# ML8511_Breakout.net
KiCad netlist of a schematic drawn in EAGLE
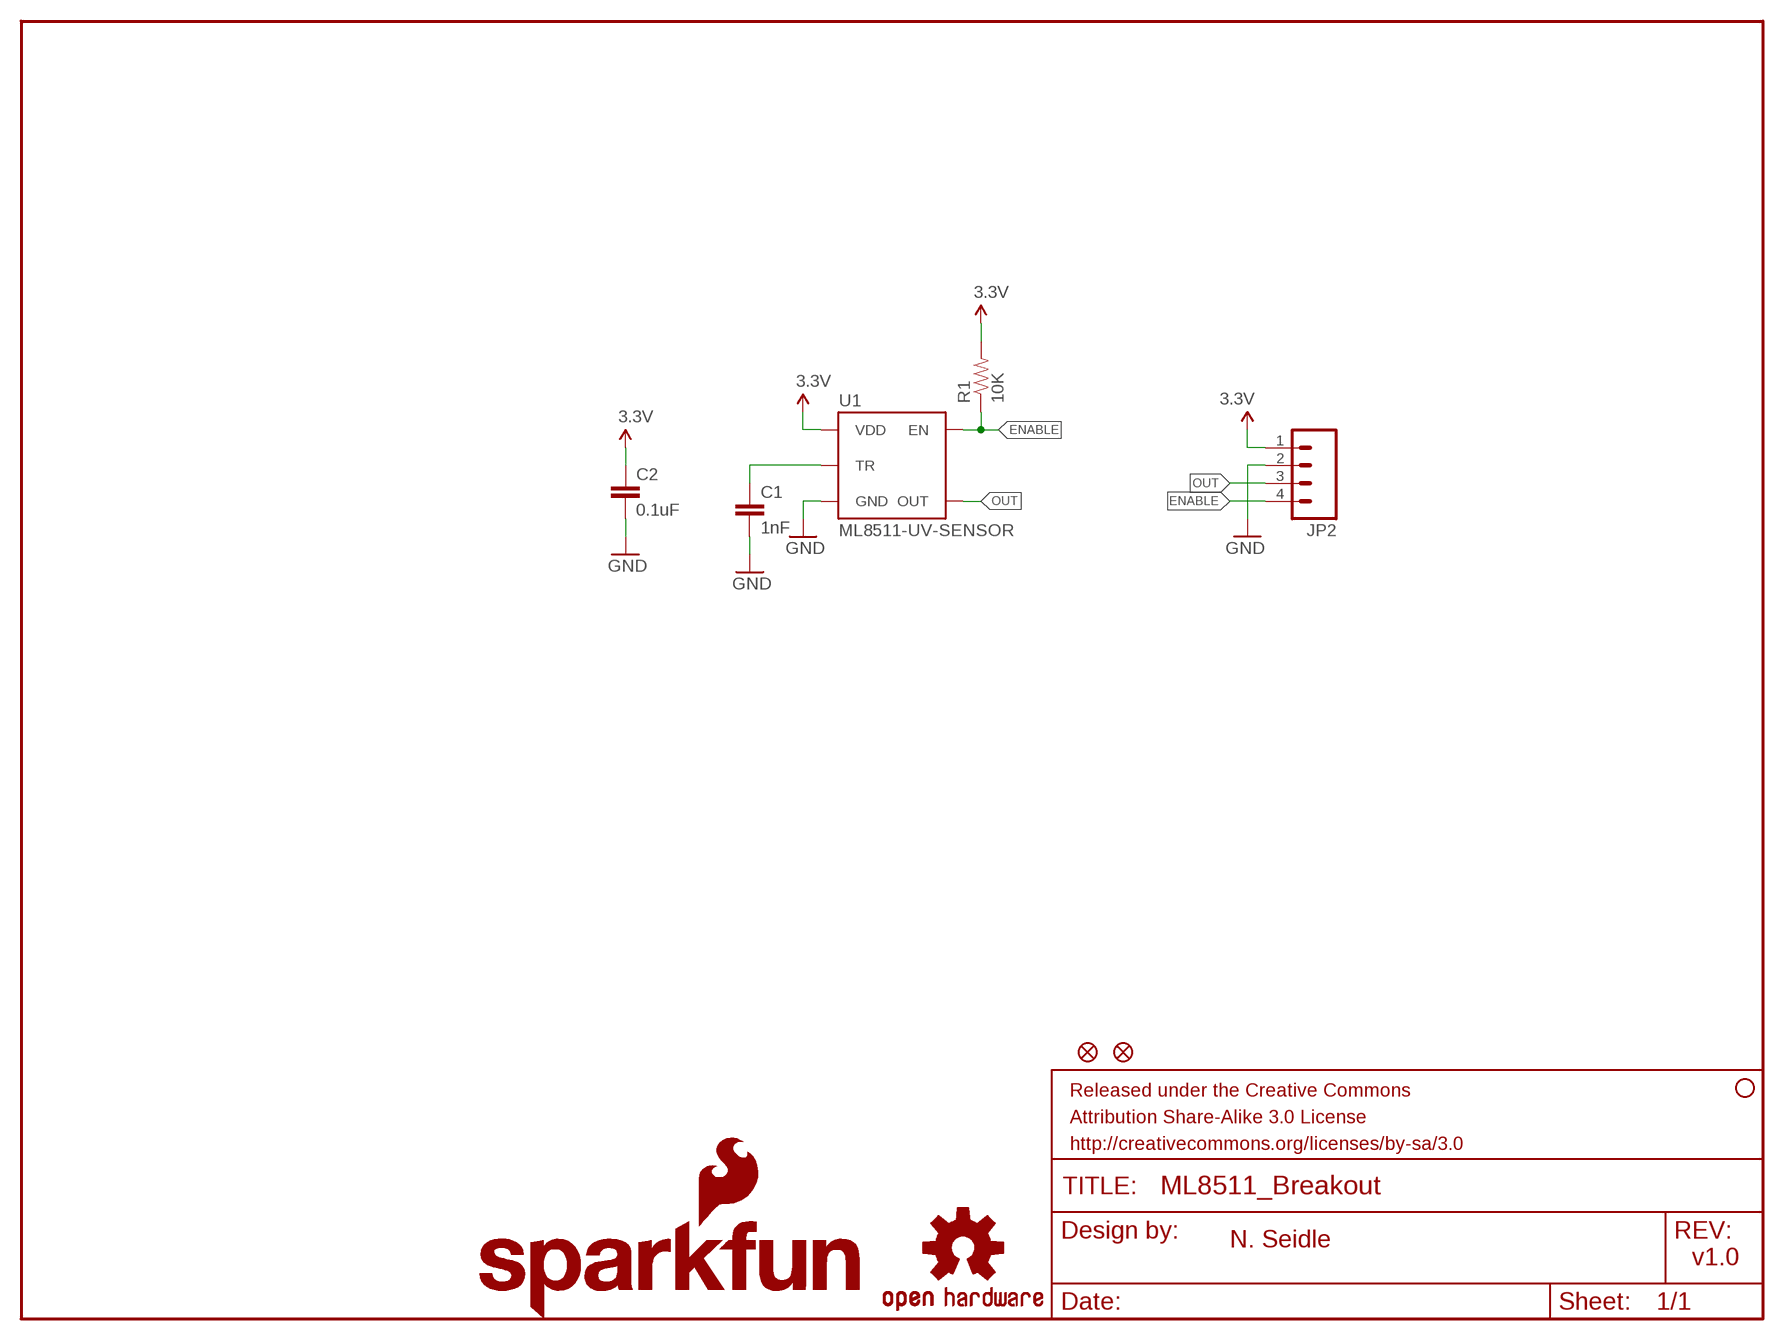
[diagram p0: schematic, sheet 1]

(export (version "E")
  (design (tool "Eeschema 10.0.6"))
  (components
    (comp (ref "C1")
      (value "1nF")
      (footprint "eagle-import:0603-CAP")
      (libsource (lib "eagle-import") (part "1NF/1000PF-50V-10%(0603)"))
    )
    (comp (ref "C2")
      (value "0.1uF")
      (footprint "eagle-import:0603-CAP")
      (libsource (lib "eagle-import") (part "0.1UF-25V(+80/-20%)(0603)"))
    )
    (comp (ref "FID1")
      (value "FIDUCIAL1X2")
      (footprint "eagle-import:FIDUCIAL-1X2")
      (libsource (lib "eagle-import") (part "FIDUCIAL1X2"))
    )
    (comp (ref "FID2")
      (value "FIDUCIAL1X2")
      (footprint "eagle-import:FIDUCIAL-1X2")
      (libsource (lib "eagle-import") (part "FIDUCIAL1X2"))
    )
    (comp (ref "FRAME2")
      (value "FRAME-LETTER")
      (footprint "eagle-import:CREATIVE_COMMONS")
      (libsource (lib "eagle-import") (part "FRAME-LETTER"))
    )
    (comp (ref "JP2")
      (value "M04PTH")
      (footprint "eagle-import:1X04")
      (libsource (lib "eagle-import") (part "M04PTH"))
    )
    (comp (ref "LOGO2")
      (value "OSHW-LOGOS")
      (footprint "eagle-import:OSHW-LOGO-S")
      (libsource (lib "eagle-import") (part "OSHW-LOGOS"))
    )
    (comp (ref "LOGO3")
      (value "SFE_LOGO_FLAME.1_INCH")
      (footprint "eagle-import:SFE_LOGO_FLAME_.1")
      (libsource (lib "eagle-import") (part "SFE_LOGO_FLAME.1_INCH"))
    )
    (comp (ref "LOGO4")
      (value "SFE_LOGO_NAME.1_INCH")
      (footprint "eagle-import:SFE_LOGO_NAME_.1")
      (libsource (lib "eagle-import") (part "SFE_LOGO_NAME.1_INCH"))
    )
    (comp (ref "R1")
      (value "10K")
      (footprint "eagle-import:0603-RES")
      (libsource (lib "eagle-import") (part "10KOHM1/10W1%(0603)0603"))
    )
    (comp (ref "STANDOFF1")
      (value "STAND-OFF")
      (footprint "eagle-import:STAND-OFF")
      (libsource (lib "eagle-import") (part "STAND-OFF"))
    )
    (comp (ref "U1")
      (value "ML8511-UV-SENSOR")
      (footprint "eagle-import:ML8511")
      (libsource (lib "eagle-import") (part "ML8511-UV-SENSORSMD"))
    )
  )
  (nets
    (net (code "1") (name "3.3V") (class "Default")
      (node (ref "C2") (pin "1") (pinfunction "1_1") (pintype "passive"))
      (node (ref "JP2") (pin "1") (pinfunction "1_1") (pintype "passive"))
      (node (ref "R1") (pin "2") (pinfunction "2_2") (pintype "passive"))
      (node (ref "U1") (pin "7") (pinfunction "VDD_7") (pintype "power_in"))
    )
    (net (code "2") (name "ENABLE") (class "Default")
      (node (ref "JP2") (pin "4") (pinfunction "4_4") (pintype "passive"))
      (node (ref "R1") (pin "1") (pinfunction "1_1") (pintype "passive"))
      (node (ref "U1") (pin "4") (pinfunction "EN_4") (pintype "input"))
    )
    (net (code "3") (name "GND") (class "Default")
      (node (ref "C1") (pin "2") (pinfunction "2_2") (pintype "passive"))
      (node (ref "C2") (pin "2") (pinfunction "2_2") (pintype "passive"))
      (node (ref "JP2") (pin "2") (pinfunction "2_2") (pintype "passive"))
      (node (ref "U1") (pin "5") (pinfunction "GND_5") (pintype "power_in"))
    )
    (net (code "4") (name "Net-(U1-TR)") (class "Default")
      (node (ref "C1") (pin "1") (pinfunction "1_1") (pintype "passive"))
      (node (ref "U1") (pin "10") (pinfunction "TR_10") (pintype "power_in"))
    )
    (net (code "5") (name "OUT") (class "Default")
      (node (ref "JP2") (pin "3") (pinfunction "3_3") (pintype "passive"))
      (node (ref "U1") (pin "8") (pinfunction "OUT_8") (pintype "output"))
    )
  )
)
